# UsbKiller.net
KiCad netlist of a schematic drawn in Altium Designer
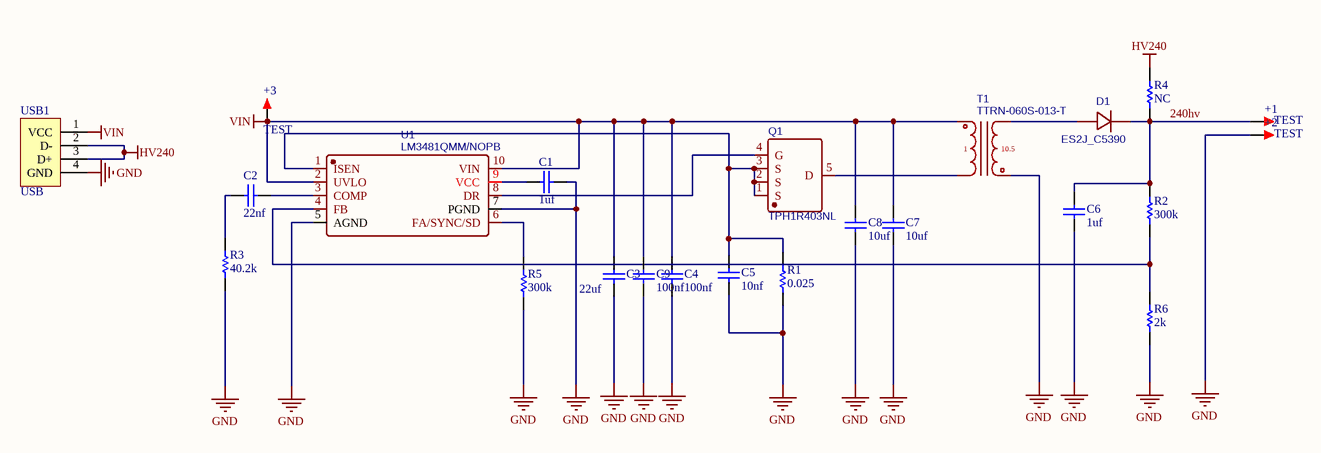
[diagram p0: UsbKiller.SchDoc]

(export (version "E")
  (design (tool "Eeschema 10.0.6"))
  (components
    (comp (ref "+1")
      (value "TEST")
      (footprint "Test Point SMD 1.0")
      (description "测试点")
      (fields (field (name "版权归属") "源创客"))
      (libsource (lib "3D Mode") (part "TEST"))
    )
    (comp (ref "+2")
      (value "TEST")
      (footprint "Test Point SMD 1.0")
      (description "测试点")
      (fields (field (name "版权归属") "源创客"))
      (libsource (lib "3D Mode") (part "TEST"))
    )
    (comp (ref "+3")
      (value "TEST")
      (footprint "Test Point SMD 1.0")
      (description "测试点")
      (fields (field (name "版权归属") "源创客"))
      (libsource (lib "3D Mode") (part "TEST"))
    )
    (comp (ref "C1")
      (value "1uf")
      (footprint "C 0603")
      (description "贴片电容")
      (fields (field (name "PUBLISHER") "Altium Limited"))
      (libsource (lib "Miscellaneous Devices") (part "Cap"))
    )
    (comp (ref "C2")
      (value "22nf")
      (footprint "C 0603")
      (description "贴片电容")
      (fields (field (name "PUBLISHER") "Altium Limited"))
      (libsource (lib "Miscellaneous Devices") (part "Cap"))
    )
    (comp (ref "C3")
      (value "22uf")
      (footprint "C 0603")
      (description "贴片电容")
      (fields (field (name "PUBLISHER") "Altium Limited"))
      (libsource (lib "Miscellaneous Devices") (part "Cap"))
    )
    (comp (ref "C4")
      (value "100nf")
      (footprint "C 0603")
      (description "贴片电容")
      (fields (field (name "PUBLISHER") "Altium Limited"))
      (libsource (lib "Miscellaneous Devices") (part "Cap"))
    )
    (comp (ref "C5")
      (value "10nf")
      (footprint "C 0603")
      (description "贴片电容")
      (fields (field (name "PUBLISHER") "Altium Limited"))
      (libsource (lib "Miscellaneous Devices") (part "Cap"))
    )
    (comp (ref "C6")
      (value "1uf")
      (footprint "1812")
      (description "贴片电容")
      (fields (field (name "PUBLISHER") "Altium Limited"))
      (libsource (lib "Miscellaneous Devices") (part "Cap"))
    )
    (comp (ref "C7")
      (value "10uf")
      (footprint "C 0805")
      (description "贴片电容")
      (fields (field (name "PUBLISHER") "Altium Limited"))
      (libsource (lib "Miscellaneous Devices") (part "Cap"))
    )
    (comp (ref "C8")
      (value "10uf")
      (footprint "C 0805")
      (description "贴片电容")
      (fields (field (name "PUBLISHER") "Altium Limited"))
      (libsource (lib "Miscellaneous Devices") (part "Cap"))
    )
    (comp (ref "C9")
      (value "100nf")
      (footprint "C 0603")
      (description "贴片电容")
      (fields (field (name "PUBLISHER") "Altium Limited"))
      (libsource (lib "Miscellaneous Devices") (part "Cap"))
    )
    (comp (ref "D1")
      (value "ES2J_C5390")
      (footprint "SMA")
      (fields (field (name "BOM_MANUFACTURER PART") "ES2J") (field (name "BOM_SUPPLIER PART") "C5390"))
      (libsource (lib "altium-import") (part "root_2_ES2J_C5390_"))
    )
    (comp (ref "Q1")
      (value "TPH1R403NL")
      (footprint "PDFN8")
      (fields (field (name "BOM_SUPPLIER PART") "C83440"))
      (libsource (lib "altium-import") (part "root_2_mirrored_TPH1R403NL_"))
    )
    (comp (ref "R1")
      (value "0.025")
      (footprint "RES 1206")
      (description "贴片电阻")
      (fields (field (name "PUBLISHER") "Altium Limited"))
      (libsource (lib "Miscellaneous Devices") (part "Res1"))
    )
    (comp (ref "R2")
      (value "300k")
      (footprint "R 0603")
      (description "贴片电阻")
      (fields (field (name "PUBLISHER") "Altium Limited"))
      (libsource (lib "Miscellaneous Devices") (part "Res1"))
    )
    (comp (ref "R3")
      (value "40.2k")
      (footprint "R 0603")
      (description "贴片电阻")
      (fields (field (name "PUBLISHER") "Altium Limited"))
      (libsource (lib "Miscellaneous Devices") (part "Res1"))
    )
    (comp (ref "R4")
      (value "NC")
      (footprint "R 0603")
      (description "贴片电阻")
      (fields (field (name "PUBLISHER") "Altium Limited"))
      (libsource (lib "Miscellaneous Devices") (part "Res1"))
    )
    (comp (ref "R5")
      (value "300k")
      (footprint "R 0603")
      (description "贴片电阻")
      (fields (field (name "PUBLISHER") "Altium Limited"))
      (libsource (lib "Miscellaneous Devices") (part "Res1"))
    )
    (comp (ref "R6")
      (value "2k")
      (footprint "R 0603")
      (description "贴片电阻")
      (fields (field (name "PUBLISHER") "Altium Limited"))
      (libsource (lib "Miscellaneous Devices") (part "Res1"))
    )
    (comp (ref "T1")
      (value "TTRN-060S-013-T")
      (footprint "TTRN-013 Dorp")
      (fields (field (name "CONTRIBUTOR") "ChaoJiSuanMiao"))
      (libsource (lib "altium-import") (part "root_0_TTRN-060S-013-T_"))
    )
    (comp (ref "U1")
      (value "LM3481QMM/NOPB")
      (footprint "VSSOP-10")
      (fields (field (name "BOM_SUPPLIER PART") "C205461") (field (name "CONTRIBUTOR") "LCSC"))
      (libsource (lib "altium-import") (part "root_0_LM3481QMM/NOPB_"))
    )
    (comp (ref "USB1")
      (value "USB")
      (footprint "USB_A/P_A")
      (description "USB-A型公接口")
      (fields (field (name "版权归属") "源创客"))
      (libsource (lib "3D Mode") (part "USB-A/P"))
    )
  )
  (nets
    (net (code "1") (name "/240hv") (class "Default")
      (node (ref "+1") (pin "1") (pinfunction "1_1") (pintype "passive"))
      (node (ref "C6") (pin "1") (pinfunction "1_1") (pintype "passive"))
      (node (ref "D1") (pin "2") (pinfunction "C_2") (pintype "passive"))
      (node (ref "R2") (pin "2") (pinfunction "2_2") (pintype "passive"))
      (node (ref "R4") (pin "1") (pinfunction "1_1") (pintype "passive"))
    )
    (net (code "2") (name "GND") (class "Default")
      (node (ref "+2") (pin "1") (pinfunction "1_1") (pintype "passive"))
      (node (ref "C1") (pin "1") (pinfunction "1_1") (pintype "passive"))
      (node (ref "C3") (pin "2") (pinfunction "2_2") (pintype "passive"))
      (node (ref "C4") (pin "2") (pinfunction "2_2") (pintype "passive"))
      (node (ref "C5") (pin "2") (pinfunction "2_2") (pintype "passive"))
      (node (ref "C6") (pin "2") (pinfunction "2_2") (pintype "passive"))
      (node (ref "C7") (pin "2") (pinfunction "2_2") (pintype "passive"))
      (node (ref "C8") (pin "2") (pinfunction "2_2") (pintype "passive"))
      (node (ref "C9") (pin "2") (pinfunction "2_2") (pintype "passive"))
      (node (ref "R1") (pin "1") (pinfunction "1_1") (pintype "passive"))
      (node (ref "R3") (pin "1") (pinfunction "1_1") (pintype "passive"))
      (node (ref "R5") (pin "1") (pinfunction "1_1") (pintype "passive"))
      (node (ref "R6") (pin "1") (pinfunction "1_1") (pintype "passive"))
      (node (ref "T1") (pin "3") (pinfunction "4_3") (pintype "passive"))
      (node (ref "U1") (pin "5") (pinfunction "AGND_5") (pintype "passive"))
      (node (ref "U1") (pin "7") (pinfunction "PGND_7") (pintype "passive"))
      (node (ref "USB1") (pin "4") (pinfunction "GND_4") (pintype "passive"))
    )
    (net (code "3") (name "HV240") (class "Default")
      (node (ref "R4") (pin "2") (pinfunction "2_2") (pintype "passive"))
      (node (ref "USB1") (pin "2") (pinfunction "D-_2") (pintype "passive"))
      (node (ref "USB1") (pin "3") (pinfunction "D+_3") (pintype "passive"))
    )
    (net (code "4") (name "Net-(C2-Pad1)") (class "Default")
      (node (ref "C2") (pin "1") (pinfunction "1_1") (pintype "passive"))
      (node (ref "R3") (pin "2") (pinfunction "2_2") (pintype "passive"))
    )
    (net (code "5") (name "Net-(D1-A)") (class "Default")
      (node (ref "D1") (pin "1") (pinfunction "A_1") (pintype "passive"))
      (node (ref "T1") (pin "2") (pinfunction "3_2") (pintype "passive"))
    )
    (net (code "6") (name "Net-(Q1-D)") (class "Default")
      (node (ref "Q1") (pin "5") (pinfunction "D_5") (pintype "passive"))
      (node (ref "T1") (pin "5") (pinfunction "2_5") (pintype "passive"))
    )
    (net (code "7") (name "Net-(Q1-G)") (class "Default")
      (node (ref "Q1") (pin "4") (pinfunction "G_4") (pintype "passive"))
      (node (ref "U1") (pin "8") (pinfunction "DR_8") (pintype "passive"))
    )
    (net (code "8") (name "Net-(U1-COMP)") (class "Default")
      (node (ref "C2") (pin "2") (pinfunction "2_2") (pintype "passive"))
      (node (ref "U1") (pin "3") (pinfunction "COMP_3") (pintype "passive"))
    )
    (net (code "9") (name "Net-(U1-FA{slash}SYNC{slash}SD)") (class "Default")
      (node (ref "R5") (pin "2") (pinfunction "2_2") (pintype "passive"))
      (node (ref "U1") (pin "6") (pinfunction "FA/SYNC/SD_6") (pintype "passive"))
    )
    (net (code "10") (name "Net-(U1-FB)") (class "Default")
      (node (ref "R2") (pin "1") (pinfunction "1_1") (pintype "passive"))
      (node (ref "R6") (pin "2") (pinfunction "2_2") (pintype "passive"))
      (node (ref "U1") (pin "4") (pinfunction "FB_4") (pintype "passive"))
    )
    (net (code "11") (name "Net-(U1-ISEN)") (class "Default")
      (node (ref "C5") (pin "1") (pinfunction "1_1") (pintype "passive"))
      (node (ref "Q1") (pin "1") (pinfunction "S_1") (pintype "passive"))
      (node (ref "Q1") (pin "2") (pinfunction "S_2") (pintype "passive"))
      (node (ref "Q1") (pin "3") (pinfunction "S_3") (pintype "passive"))
      (node (ref "R1") (pin "2") (pinfunction "2_2") (pintype "passive"))
      (node (ref "U1") (pin "1") (pinfunction "ISEN_1") (pintype "passive"))
    )
    (net (code "12") (name "Net-(U1-VCC)") (class "Default")
      (node (ref "C1") (pin "2") (pinfunction "2_2") (pintype "passive"))
      (node (ref "U1") (pin "9") (pinfunction "VCC_9") (pintype "passive"))
    )
    (net (code "13") (name "VIN") (class "Default")
      (node (ref "+3") (pin "1") (pinfunction "1_1") (pintype "passive"))
      (node (ref "C3") (pin "1") (pinfunction "1_1") (pintype "passive"))
      (node (ref "C4") (pin "1") (pinfunction "1_1") (pintype "passive"))
      (node (ref "C7") (pin "1") (pinfunction "1_1") (pintype "passive"))
      (node (ref "C8") (pin "1") (pinfunction "1_1") (pintype "passive"))
      (node (ref "C9") (pin "1") (pinfunction "1_1") (pintype "passive"))
      (node (ref "T1") (pin "1") (pinfunction "1_1") (pintype "passive"))
      (node (ref "U1") (pin "10") (pinfunction "VIN_10") (pintype "passive"))
      (node (ref "U1") (pin "2") (pinfunction "UVLO_2") (pintype "passive"))
      (node (ref "USB1") (pin "1") (pinfunction "VCC_1") (pintype "passive"))
    )
  )
)
